# Error_Generator.net
KiCad netlist of a schematic drawn in Altium Designer
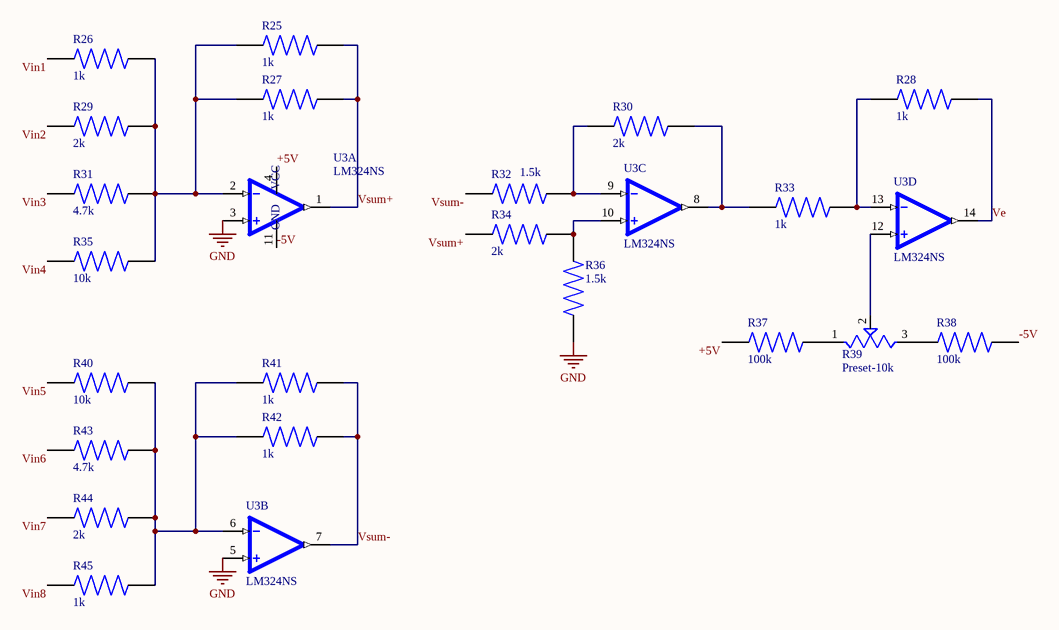
[diagram p0: Error_Generator.SchDoc]

(export (version "E")
  (design (tool "Eeschema 10.0.6"))
  (components
    (comp (ref "R25")
      (value "1k")
      (footprint "RESC2012X60N")
      (fields
        (field (name "DIGIKEY_PART_NUMBER") "311-1.00KCRTR-ND")
        (field (name "MF") "Yageo")
        (field (name "MP") "RC0805FR-071KL")
      )
      (libsource (lib "1ks") (part "1k"))
    )
    (comp (ref "R26")
      (value "1k")
      (footprint "RESC2012X60N")
      (fields
        (field (name "DIGIKEY_PART_NUMBER") "311-1.00KCRTR-ND")
        (field (name "MF") "Yageo")
        (field (name "MP") "RC0805FR-071KL")
      )
      (libsource (lib "1ks") (part "1k"))
    )
    (comp (ref "R27")
      (value "1k")
      (footprint "RESC2012X60N")
      (fields
        (field (name "DIGIKEY_PART_NUMBER") "311-1.00KCRTR-ND")
        (field (name "MF") "Yageo")
        (field (name "MP") "RC0805FR-071KL")
      )
      (libsource (lib "1ks") (part "1k"))
    )
    (comp (ref "R28")
      (value "1k")
      (footprint "RESC2012X60N")
      (fields
        (field (name "DIGIKEY_PART_NUMBER") "311-1.00KCRTR-ND")
        (field (name "MF") "Yageo")
        (field (name "MP") "RC0805FR-071KL")
      )
      (libsource (lib "1ks") (part "1k"))
    )
    (comp (ref "R29")
      (value "2k")
      (footprint "RESC2012X60N")
      (fields (field (name "MF") "Yageo") (field (name "MP") "RC0805FR-072KL"))
      (libsource (lib "2ks") (part "2k"))
    )
    (comp (ref "R30")
      (value "2k")
      (footprint "RESC2012X60N")
      (fields (field (name "MF") "Yageo") (field (name "MP") "RC0805FR-072KL"))
      (libsource (lib "2ks") (part "2k"))
    )
    (comp (ref "R31")
      (value "4.7k")
      (footprint "RESC2012X60N")
      (fields (field (name "MP") "RC0805FR-074K7L") (field (name "MF") "Yageo"))
      (libsource (lib "4 7ks") (part "4.7k"))
    )
    (comp (ref "R32")
      (value "1.5k")
      (footprint "RESC2012X60N")
      (description "Res Thin Film 0805 1.5K Ohm 0.1% 0.125W(1/8W) Â±25ppm/C Epoxy Pad SMD T/R; RT0805BRD071K5L")
      (fields (field (name "MF") "Yageo") (field (name "MP") "RT0805BRD071K5L"))
      (libsource (lib "1 5ks") (part "1.5k"))
    )
    (comp (ref "R33")
      (value "1k")
      (footprint "RESC2012X60N")
      (fields
        (field (name "DIGIKEY_PART_NUMBER") "311-1.00KCRTR-ND")
        (field (name "MF") "Yageo")
        (field (name "MP") "RC0805FR-071KL")
      )
      (libsource (lib "1ks") (part "1k"))
    )
    (comp (ref "R34")
      (value "2k")
      (footprint "RESC2012X60N")
      (fields (field (name "MF") "Yageo") (field (name "MP") "RC0805FR-072KL"))
      (libsource (lib "2ks") (part "2k"))
    )
    (comp (ref "R35")
      (value "10k")
      (footprint "RESC2012X60N")
      (fields (field (name "MF") "Yageo") (field (name "MP") "RC0805FR-0710KL"))
      (libsource (lib "10ks") (part "10k"))
    )
    (comp (ref "R36")
      (value "1.5k")
      (footprint "RESC2012X60N")
      (description "Res Thin Film 0805 1.5K Ohm 0.1% 0.125W(1/8W) Â±25ppm/C Epoxy Pad SMD T/R; RT0805BRD071K5L")
      (fields (field (name "MF") "Yageo") (field (name "MP") "RT0805BRD071K5L"))
      (libsource (lib "1 5ks") (part "1.5k"))
    )
    (comp (ref "R37")
      (value "100k")
      (footprint "RESC2012X60N")
      (fields (field (name "MF") "Yageo") (field (name "MP") "RC0805FR-07100KL"))
      (libsource (lib "100ks") (part "100k"))
    )
    (comp (ref "R38")
      (value "100k")
      (footprint "RESC2012X60N")
      (fields (field (name "MF") "Yageo") (field (name "MP") "RC0805FR-07100KL"))
      (libsource (lib "100ks") (part "100k"))
    )
    (comp (ref "R39")
      (value "Preset-10k")
      (footprint "TRIM_3306F-1-103")
      (description "TRIMMER - 6MM ROUND, SINGLE-TURN,CERMET, 10K OHMS ¦ Bourns 3306F-1-103")
      (fields (field (name "MF") "Bourns") (field (name "MP") "3306F-1-103"))
      (libsource (lib "3306F-1-103") (part "Preset"))
    )
    (comp (ref "R40")
      (value "10k")
      (footprint "RESC2012X60N")
      (fields (field (name "MF") "Yageo") (field (name "MP") "RC0805FR-0710KL"))
      (libsource (lib "10ks") (part "10k"))
    )
    (comp (ref "R41")
      (value "1k")
      (footprint "RESC2012X60N")
      (fields
        (field (name "DIGIKEY_PART_NUMBER") "311-1.00KCRTR-ND")
        (field (name "MF") "Yageo")
        (field (name "MP") "RC0805FR-071KL")
      )
      (libsource (lib "1ks") (part "1k"))
    )
    (comp (ref "R42")
      (value "1k")
      (footprint "RESC2012X60N")
      (fields
        (field (name "DIGIKEY_PART_NUMBER") "311-1.00KCRTR-ND")
        (field (name "MF") "Yageo")
        (field (name "MP") "RC0805FR-071KL")
      )
      (libsource (lib "1ks") (part "1k"))
    )
    (comp (ref "R43")
      (value "4.7k")
      (footprint "RESC2012X60N")
      (fields (field (name "MP") "RC0805FR-074K7L") (field (name "MF") "Yageo"))
      (libsource (lib "4 7ks") (part "4.7k"))
    )
    (comp (ref "R44")
      (value "2k")
      (footprint "RESC2012X60N")
      (fields (field (name "MF") "Yageo") (field (name "MP") "RC0805FR-072KL"))
      (libsource (lib "2ks") (part "2k"))
    )
    (comp (ref "R45")
      (value "1k")
      (footprint "RESC2012X60N")
      (fields
        (field (name "DIGIKEY_PART_NUMBER") "311-1.00KCRTR-ND")
        (field (name "MF") "Yageo")
        (field (name "MP") "RC0805FR-071KL")
      )
      (libsource (lib "1ks") (part "1k"))
    )
    (comp (ref "U3")
      (value "LM324NS")
      (footprint "SOIC127P780X200-14N")
      (description "4-Channel industry standard operational amplifier 14-SO 0 to 70; LM324NSRG4")
      (fields (field (name "MP") "LM324NSRG4") (field (name "MF") "Texas Instruments"))
      (libsource (lib "LM324NSRG4") (part "LM324NS"))
    )
  )
  (nets
    (net (code "1") (name "/+5V") (class "Default")
      (node (ref "R37") (pin "1") (pinfunction "1_1") (pintype "passive"))
      (node (ref "U3") (pin "4") (pinfunction "VCC_4") (pintype "power_in"))
    )
    (net (code "2") (name "/-5V") (class "Default")
      (node (ref "R38") (pin "2") (pinfunction "2_2") (pintype "passive"))
      (node (ref "U3") (pin "11") (pinfunction "GND_11") (pintype "power_in"))
    )
    (net (code "3") (name "/Ve") (class "Default")
      (node (ref "R28") (pin "2") (pinfunction "2_2") (pintype "passive"))
      (node (ref "U3") (pin "14") (pinfunction "4OUT_14") (pintype "output"))
    )
    (net (code "4") (name "/Vin1") (class "Default")
      (node (ref "R26") (pin "1") (pinfunction "1_1") (pintype "passive"))
    )
    (net (code "5") (name "/Vin2") (class "Default")
      (node (ref "R29") (pin "1") (pinfunction "1_1") (pintype "passive"))
    )
    (net (code "6") (name "/Vin3") (class "Default")
      (node (ref "R31") (pin "1") (pinfunction "1_1") (pintype "passive"))
    )
    (net (code "7") (name "/Vin4") (class "Default")
      (node (ref "R35") (pin "1") (pinfunction "1_1") (pintype "passive"))
    )
    (net (code "8") (name "/Vin5") (class "Default")
      (node (ref "R40") (pin "1") (pinfunction "1_1") (pintype "passive"))
    )
    (net (code "9") (name "/Vin6") (class "Default")
      (node (ref "R43") (pin "1") (pinfunction "1_1") (pintype "passive"))
    )
    (net (code "10") (name "/Vin7") (class "Default")
      (node (ref "R44") (pin "1") (pinfunction "1_1") (pintype "passive"))
    )
    (net (code "11") (name "/Vin8") (class "Default")
      (node (ref "R45") (pin "1") (pinfunction "1_1") (pintype "passive"))
    )
    (net (code "12") (name "/Vsum+") (class "Default")
      (node (ref "R25") (pin "2") (pinfunction "2_2") (pintype "passive"))
      (node (ref "R27") (pin "2") (pinfunction "2_2") (pintype "passive"))
      (node (ref "R34") (pin "1") (pinfunction "1_1") (pintype "passive"))
      (node (ref "U3") (pin "1") (pinfunction "1OUT_1") (pintype "output"))
    )
    (net (code "13") (name "/Vsum-") (class "Default")
      (node (ref "R32") (pin "1") (pinfunction "1_1") (pintype "passive"))
      (node (ref "R41") (pin "2") (pinfunction "2_2") (pintype "passive"))
      (node (ref "R42") (pin "2") (pinfunction "2_2") (pintype "passive"))
      (node (ref "U3") (pin "7") (pinfunction "2OUT_7") (pintype "output"))
    )
    (net (code "14") (name "GND") (class "Default")
      (node (ref "R36") (pin "1") (pinfunction "1_1") (pintype "passive"))
      (node (ref "U3") (pin "3") (pinfunction "1IN+_3") (pintype "input"))
      (node (ref "U3") (pin "5") (pinfunction "2IN+_5") (pintype "input"))
    )
    (net (code "15") (name "Net-(R39-CCW)") (class "Default")
      (node (ref "R37") (pin "2") (pinfunction "2_2") (pintype "passive"))
      (node (ref "R39") (pin "1") (pinfunction "CCW_1") (pintype "passive"))
    )
    (net (code "16") (name "Net-(R39-CW)") (class "Default")
      (node (ref "R38") (pin "1") (pinfunction "1_1") (pintype "passive"))
      (node (ref "R39") (pin "3") (pinfunction "CW_3") (pintype "passive"))
    )
    (net (code "17") (name "Net-(R39-W)") (class "Default")
      (node (ref "R39") (pin "2") (pinfunction "W_2") (pintype "passive"))
      (node (ref "U3") (pin "12") (pinfunction "4IN+_12") (pintype "input"))
    )
    (net (code "18") (name "Net-(U3A-1IN-)") (class "Default")
      (node (ref "R25") (pin "1") (pinfunction "1_1") (pintype "passive"))
      (node (ref "R26") (pin "2") (pinfunction "2_2") (pintype "passive"))
      (node (ref "R27") (pin "1") (pinfunction "1_1") (pintype "passive"))
      (node (ref "R29") (pin "2") (pinfunction "2_2") (pintype "passive"))
      (node (ref "R31") (pin "2") (pinfunction "2_2") (pintype "passive"))
      (node (ref "R35") (pin "2") (pinfunction "2_2") (pintype "passive"))
      (node (ref "U3") (pin "2") (pinfunction "1IN-_2") (pintype "input"))
    )
    (net (code "19") (name "Net-(U3B-2IN-)") (class "Default")
      (node (ref "R40") (pin "2") (pinfunction "2_2") (pintype "passive"))
      (node (ref "R41") (pin "1") (pinfunction "1_1") (pintype "passive"))
      (node (ref "R42") (pin "1") (pinfunction "1_1") (pintype "passive"))
      (node (ref "R43") (pin "2") (pinfunction "2_2") (pintype "passive"))
      (node (ref "R44") (pin "2") (pinfunction "2_2") (pintype "passive"))
      (node (ref "R45") (pin "2") (pinfunction "2_2") (pintype "passive"))
      (node (ref "U3") (pin "6") (pinfunction "2IN-_6") (pintype "input"))
    )
    (net (code "20") (name "Net-(U3C-3IN+)") (class "Default")
      (node (ref "R34") (pin "2") (pinfunction "2_2") (pintype "passive"))
      (node (ref "R36") (pin "2") (pinfunction "2_2") (pintype "passive"))
      (node (ref "U3") (pin "10") (pinfunction "3IN+_10") (pintype "input"))
    )
    (net (code "21") (name "Net-(U3C-3IN-)") (class "Default")
      (node (ref "R30") (pin "1") (pinfunction "1_1") (pintype "passive"))
      (node (ref "R32") (pin "2") (pinfunction "2_2") (pintype "passive"))
      (node (ref "U3") (pin "9") (pinfunction "3IN-_9") (pintype "input"))
    )
    (net (code "22") (name "Net-(U3C-3OUT)") (class "Default")
      (node (ref "R30") (pin "2") (pinfunction "2_2") (pintype "passive"))
      (node (ref "R33") (pin "1") (pinfunction "1_1") (pintype "passive"))
      (node (ref "U3") (pin "8") (pinfunction "3OUT_8") (pintype "output"))
    )
    (net (code "23") (name "Net-(U3D-4IN-)") (class "Default")
      (node (ref "R28") (pin "1") (pinfunction "1_1") (pintype "passive"))
      (node (ref "R33") (pin "2") (pinfunction "2_2") (pintype "passive"))
      (node (ref "U3") (pin "13") (pinfunction "4IN-_13") (pintype "input"))
    )
  )
)
